# Sensors.net
KiCad netlist of a schematic drawn in Altium Designer
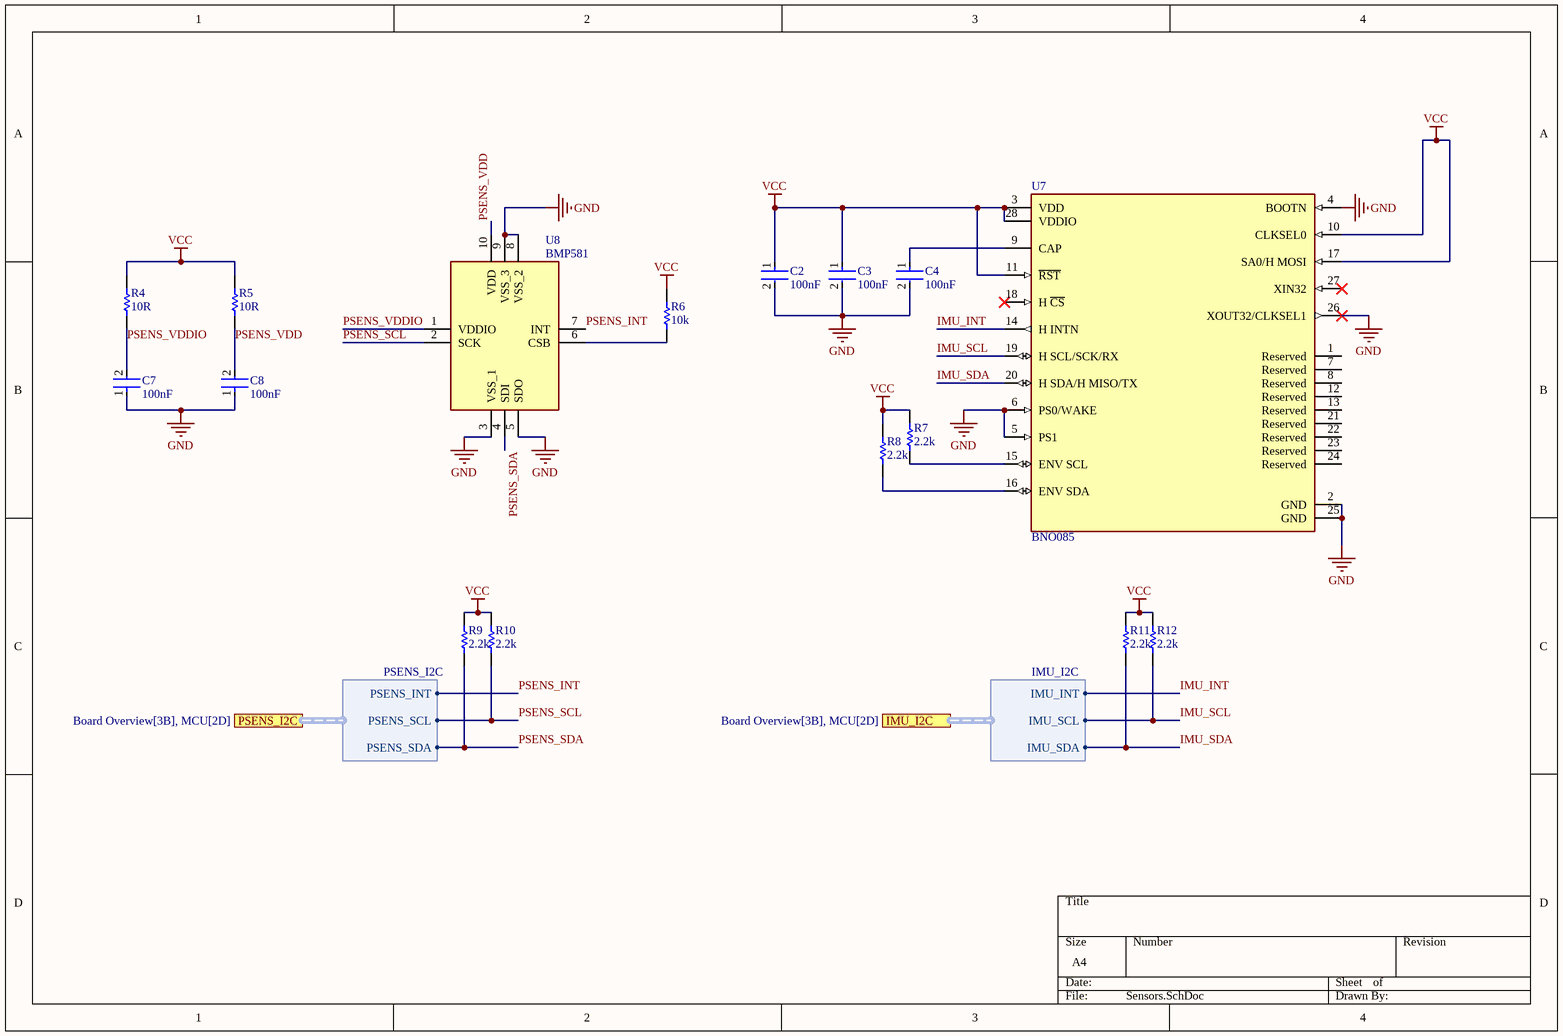
[diagram p0: Sensors.SchDoc]

(export (version "E")
  (design (tool "Eeschema 10.0.6"))
  (components
    (comp (ref "C2")
      (value "100nF")
      (footprint "FP-0603-L_1_6_0_15-W_0_81-IPC_C")
      (description "Generic 0603 Capacitor")
      (fields (field (name "LCSC PART #") "C14663") (field (name "TOLERANCE") "10%"))
      (libsource (lib "StrathSEDS") (part "02cd4be3c70576c341d710602a673aa"))
    )
    (comp (ref "C3")
      (value "100nF")
      (footprint "FP-0603-L_1_6_0_15-W_0_81-IPC_C")
      (description "Generic 0603 Capacitor")
      (fields (field (name "LCSC PART #") "C14663") (field (name "TOLERANCE") "10%"))
      (libsource (lib "StrathSEDS") (part "02cd4be3c70576c341d710602a673aa"))
    )
    (comp (ref "C4")
      (value "100nF")
      (footprint "FP-0603-L_1_6_0_15-W_0_81-IPC_C")
      (description "Generic 0603 Capacitor")
      (fields (field (name "LCSC PART #") "C14663") (field (name "TOLERANCE") "10%"))
      (libsource (lib "StrathSEDS") (part "02cd4be3c70576c341d710602a673aa"))
    )
    (comp (ref "C7")
      (value "100nF")
      (footprint "FP-0603-L_1_6_0_15-W_0_81-IPC_C")
      (description "Generic 0603 Capacitor")
      (fields (field (name "TOLERANCE") "10%") (field (name "LCSC PART #") "C14663"))
      (libsource (lib "StrathSEDS") (part "02cd4be3c70576c341d710602a673aa"))
    )
    (comp (ref "C8")
      (value "100nF")
      (footprint "FP-0603-L_1_6_0_15-W_0_81-IPC_C")
      (description "Generic 0603 Capacitor")
      (fields (field (name "TOLERANCE") "10%") (field (name "LCSC PART #") "C14663"))
      (libsource (lib "StrathSEDS") (part "02cd4be3c70576c341d710602a673aa"))
    )
    (comp (ref "R4")
      (value "10R")
      (footprint "RESC1609X50X30ML8T20")
      (description "Generic 0603 Resistor")
      (fields (field (name "TOLERANCE") "0%") (field (name "LCSC PART #") "C22859"))
      (libsource (lib "StrathSEDS") (part "RES-2"))
    )
    (comp (ref "R5")
      (value "10R")
      (footprint "RESC1609X50X30ML8T20")
      (description "Generic 0603 Resistor")
      (fields (field (name "TOLERANCE") "0%") (field (name "LCSC PART #") "C22859"))
      (libsource (lib "StrathSEDS") (part "RES-2"))
    )
    (comp (ref "R6")
      (value "10k")
      (footprint "RESC1609X50X30ML8T20")
      (description "Generic 0603 Resistor")
      (fields (field (name "TOLERANCE") "0%") (field (name "LCSC PART #") "C25804"))
      (libsource (lib "StrathSEDS") (part "RES-2"))
    )
    (comp (ref "R7")
      (value "2.2k")
      (footprint "RESC1609X50X30ML8T20")
      (description "Generic 0603 Resistor")
      (fields (field (name "TOLERANCE") "0%") (field (name "LCSC PART #") "C4190"))
      (libsource (lib "StrathSEDS") (part "RES-2"))
    )
    (comp (ref "R8")
      (value "2.2k")
      (footprint "RESC1609X50X30ML8T20")
      (description "Generic 0603 Resistor")
      (fields (field (name "TOLERANCE") "0%") (field (name "LCSC PART #") "C4190"))
      (libsource (lib "StrathSEDS") (part "RES-2"))
    )
    (comp (ref "R9")
      (value "2.2k")
      (footprint "RESC1609X50X30ML8T20")
      (description "Generic 0603 Resistor")
      (fields (field (name "TOLERANCE") "0%") (field (name "LCSC PART #") "C4190"))
      (libsource (lib "StrathSEDS") (part "RES-2"))
    )
    (comp (ref "R10")
      (value "2.2k")
      (footprint "RESC1609X50X30ML8T20")
      (description "Generic 0603 Resistor")
      (fields (field (name "TOLERANCE") "0%") (field (name "LCSC PART #") "C4190"))
      (libsource (lib "StrathSEDS") (part "RES-2"))
    )
    (comp (ref "R11")
      (value "2.2k")
      (footprint "RESC1609X50X30ML8T20")
      (description "Generic 0603 Resistor")
      (fields (field (name "TOLERANCE") "0%") (field (name "LCSC PART #") "C4190"))
      (libsource (lib "StrathSEDS") (part "RES-2"))
    )
    (comp (ref "R12")
      (value "2.2k")
      (footprint "RESC1609X50X30ML8T20")
      (description "Generic 0603 Resistor")
      (fields (field (name "TOLERANCE") "0%") (field (name "LCSC PART #") "C4190"))
      (libsource (lib "StrathSEDS") (part "RES-2"))
    )
    (comp (ref "U7")
      (value "BNO085")
      (footprint "FP-BNO085-MFG")
      (description "IMU Accel/gyro/mag I2C 32 Bit")
      (libsource (lib "StrathSEDS") (part "87552c951d161a888c2c69b58ce40bc"))
    )
    (comp (ref "U8")
      (value "BMP581")
      (footprint "BMP581")
      (description "Pressure Sensor 4.35PSI ~ 18.13PSI (30kPa ~ 125kPa) Absolute 10-WFLGA")
      (fields (field (name "MOUSER PART NUMBER") "262-BMP581"))
      (libsource (lib "StrathSEDS") (part "BMP581"))
    )
  )
  (nets
    (net (code "3") (name "/IMU_INT") (class "Default")
      (node (ref "U7") (pin "14") (pinfunction "H_INTN_14") (pintype "output"))
    )
    (net (code "4") (name "/IMU_SCL") (class "Default")
      (node (ref "R12") (pin "2") (pinfunction "2_2") (pintype "passive"))
      (node (ref "U7") (pin "19") (pinfunction "H_SCL/SCK/RX_19") (pintype "bidirectional"))
    )
    (net (code "5") (name "/IMU_SDA") (class "Default")
      (node (ref "R11") (pin "2") (pinfunction "2_2") (pintype "passive"))
      (node (ref "U7") (pin "20") (pinfunction "H_SDA/H_MISO/TX_20") (pintype "bidirectional"))
    )
    (net (code "6") (name "/PSENS_INT") (class "Default")
      (node (ref "U8") (pin "7") (pinfunction "INT_7") (pintype "passive"))
    )
    (net (code "7") (name "/PSENS_SCL") (class "Default")
      (node (ref "R10") (pin "2") (pinfunction "2_2") (pintype "passive"))
      (node (ref "U8") (pin "2") (pinfunction "SCK_2") (pintype "passive"))
    )
    (net (code "8") (name "/PSENS_SDA") (class "Default")
      (node (ref "R9") (pin "2") (pinfunction "2_2") (pintype "passive"))
      (node (ref "U8") (pin "4") (pinfunction "SDI_4") (pintype "passive"))
    )
    (net (code "9") (name "/PSENS_VDD") (class "Default")
      (node (ref "C8") (pin "2") (pinfunction "2_2") (pintype "passive"))
      (node (ref "R5") (pin "1") (pinfunction "1_1") (pintype "passive"))
      (node (ref "U8") (pin "10") (pinfunction "VDD_10") (pintype "passive"))
    )
    (net (code "10") (name "/PSENS_VDDIO") (class "Default")
      (node (ref "C7") (pin "2") (pinfunction "2_2") (pintype "passive"))
      (node (ref "R4") (pin "1") (pinfunction "1_1") (pintype "passive"))
      (node (ref "U8") (pin "1") (pinfunction "VDDIO_1") (pintype "passive"))
    )
    (net (code "13") (name "GND") (class "Default")
      (node (ref "C2") (pin "2") (pinfunction "2_2") (pintype "passive"))
      (node (ref "C3") (pin "2") (pinfunction "2_2") (pintype "passive"))
      (node (ref "C4") (pin "2") (pinfunction "2_2") (pintype "passive"))
      (node (ref "C7") (pin "1") (pinfunction "1_1") (pintype "passive"))
      (node (ref "C8") (pin "1") (pinfunction "1_1") (pintype "passive"))
      (node (ref "U7") (pin "2") (pinfunction "GND_2") (pintype "power_in"))
      (node (ref "U7") (pin "25") (pinfunction "GND_25") (pintype "power_in"))
      (node (ref "U7") (pin "26") (pinfunction "XOUT32/CLKSEL1_26") (pintype "output"))
      (node (ref "U7") (pin "4") (pinfunction "BOOTN_4") (pintype "input"))
      (node (ref "U7") (pin "5") (pinfunction "PS1_5") (pintype "input"))
      (node (ref "U7") (pin "6") (pinfunction "PS0/WAKE_6") (pintype "input"))
      (node (ref "U8") (pin "3") (pinfunction "VSS_1_3") (pintype "passive"))
      (node (ref "U8") (pin "5") (pinfunction "SDO_5") (pintype "passive"))
      (node (ref "U8") (pin "8") (pinfunction "VSS_2_8") (pintype "passive"))
      (node (ref "U8") (pin "9") (pinfunction "VSS_3_9") (pintype "passive"))
    )
    (net (code "14") (name "Net-(U7-CAP)") (class "Default")
      (node (ref "C4") (pin "1") (pinfunction "1_1") (pintype "passive"))
      (node (ref "U7") (pin "9") (pinfunction "CAP_9") (pintype "passive"))
    )
    (net (code "15") (name "Net-(U7-ENV_SCL)") (class "Default")
      (node (ref "R7") (pin "2") (pinfunction "2_2") (pintype "passive"))
      (node (ref "U7") (pin "15") (pinfunction "ENV_SCL_15") (pintype "bidirectional"))
    )
    (net (code "16") (name "Net-(U7-ENV_SDA)") (class "Default")
      (node (ref "R8") (pin "2") (pinfunction "2_2") (pintype "passive"))
      (node (ref "U7") (pin "16") (pinfunction "ENV_SDA_16") (pintype "bidirectional"))
    )
    (net (code "17") (name "Net-(U8-CSB)") (class "Default")
      (node (ref "R6") (pin "1") (pinfunction "1_1") (pintype "passive"))
      (node (ref "U8") (pin "6") (pinfunction "CSB_6") (pintype "passive"))
    )
    (net (code "18") (name "VCC") (class "Default")
      (node (ref "C2") (pin "1") (pinfunction "1_1") (pintype "passive"))
      (node (ref "C3") (pin "1") (pinfunction "1_1") (pintype "passive"))
      (node (ref "R10") (pin "1") (pinfunction "1_1") (pintype "passive"))
      (node (ref "R11") (pin "1") (pinfunction "1_1") (pintype "passive"))
      (node (ref "R12") (pin "1") (pinfunction "1_1") (pintype "passive"))
      (node (ref "R4") (pin "2") (pinfunction "2_2") (pintype "passive"))
      (node (ref "R5") (pin "2") (pinfunction "2_2") (pintype "passive"))
      (node (ref "R6") (pin "2") (pinfunction "2_2") (pintype "passive"))
      (node (ref "R7") (pin "1") (pinfunction "1_1") (pintype "passive"))
      (node (ref "R8") (pin "1") (pinfunction "1_1") (pintype "passive"))
      (node (ref "R9") (pin "1") (pinfunction "1_1") (pintype "passive"))
      (node (ref "U7") (pin "10") (pinfunction "CLKSEL0_10") (pintype "input"))
      (node (ref "U7") (pin "11") (pinfunction "~{RST}_11") (pintype "input"))
      (node (ref "U7") (pin "17") (pinfunction "SA0/H_MOSI_17") (pintype "input"))
      (node (ref "U7") (pin "28") (pinfunction "VDDIO_28") (pintype "power_in"))
      (node (ref "U7") (pin "3") (pinfunction "VDD_3") (pintype "power_in"))
    )
    (net (code "19") (name "unconnected-(U7-H_~{CS}-Pad18)") (class "Default")
      (node (ref "U7") (pin "18") (pinfunction "H_~{CS}_18") (pintype "input+no_connect"))
    )
    (net (code "20") (name "unconnected-(U7-Reserved-Pad1)") (class "Default")
      (node (ref "U7") (pin "1") (pinfunction "Reserved_1") (pintype "passive"))
    )
    (net (code "21") (name "unconnected-(U7-Reserved-Pad7)") (class "Default")
      (node (ref "U7") (pin "7") (pinfunction "Reserved_7") (pintype "passive"))
    )
    (net (code "22") (name "unconnected-(U7-Reserved-Pad8)") (class "Default")
      (node (ref "U7") (pin "8") (pinfunction "Reserved_8") (pintype "passive"))
    )
    (net (code "23") (name "unconnected-(U7-Reserved-Pad12)") (class "Default")
      (node (ref "U7") (pin "12") (pinfunction "Reserved_12") (pintype "passive"))
    )
    (net (code "24") (name "unconnected-(U7-Reserved-Pad13)") (class "Default")
      (node (ref "U7") (pin "13") (pinfunction "Reserved_13") (pintype "passive"))
    )
    (net (code "25") (name "unconnected-(U7-Reserved-Pad21)") (class "Default")
      (node (ref "U7") (pin "21") (pinfunction "Reserved_21") (pintype "passive"))
    )
    (net (code "26") (name "unconnected-(U7-Reserved-Pad22)") (class "Default")
      (node (ref "U7") (pin "22") (pinfunction "Reserved_22") (pintype "passive"))
    )
    (net (code "27") (name "unconnected-(U7-Reserved-Pad23)") (class "Default")
      (node (ref "U7") (pin "23") (pinfunction "Reserved_23") (pintype "passive"))
    )
    (net (code "28") (name "unconnected-(U7-Reserved-Pad24)") (class "Default")
      (node (ref "U7") (pin "24") (pinfunction "Reserved_24") (pintype "passive"))
    )
    (net (code "29") (name "unconnected-(U7-XIN32-Pad27)") (class "Default")
      (node (ref "U7") (pin "27") (pinfunction "XIN32_27") (pintype "input+no_connect"))
    )
  )
)
